# doodle_with_onboard_clock_smd_7805_l293d.net
KiCad netlist of a schematic drawn in EAGLE
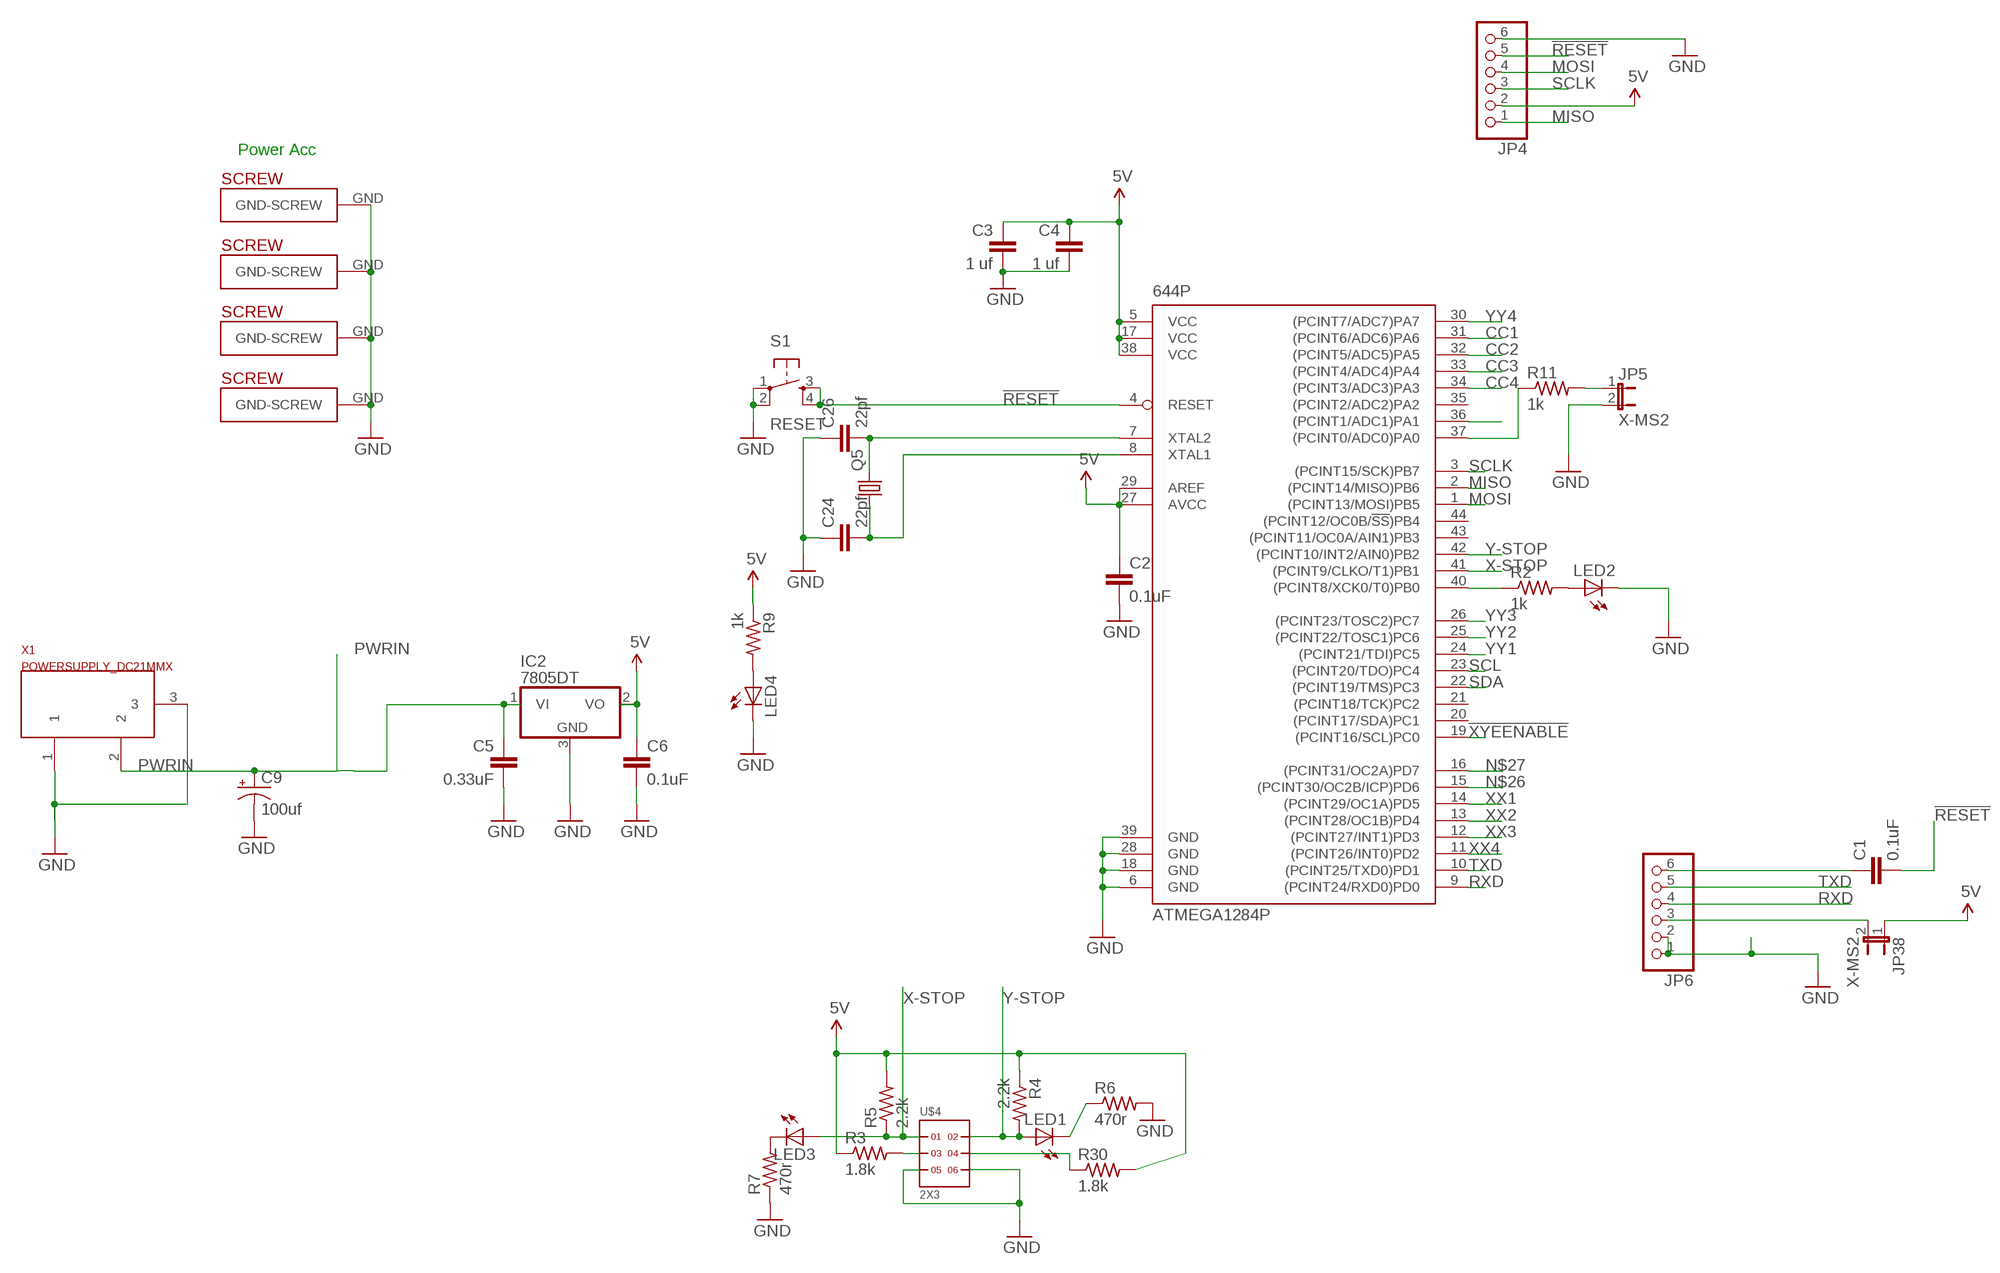
[diagram p0: schematic, sheet 1, part 1 of 2]
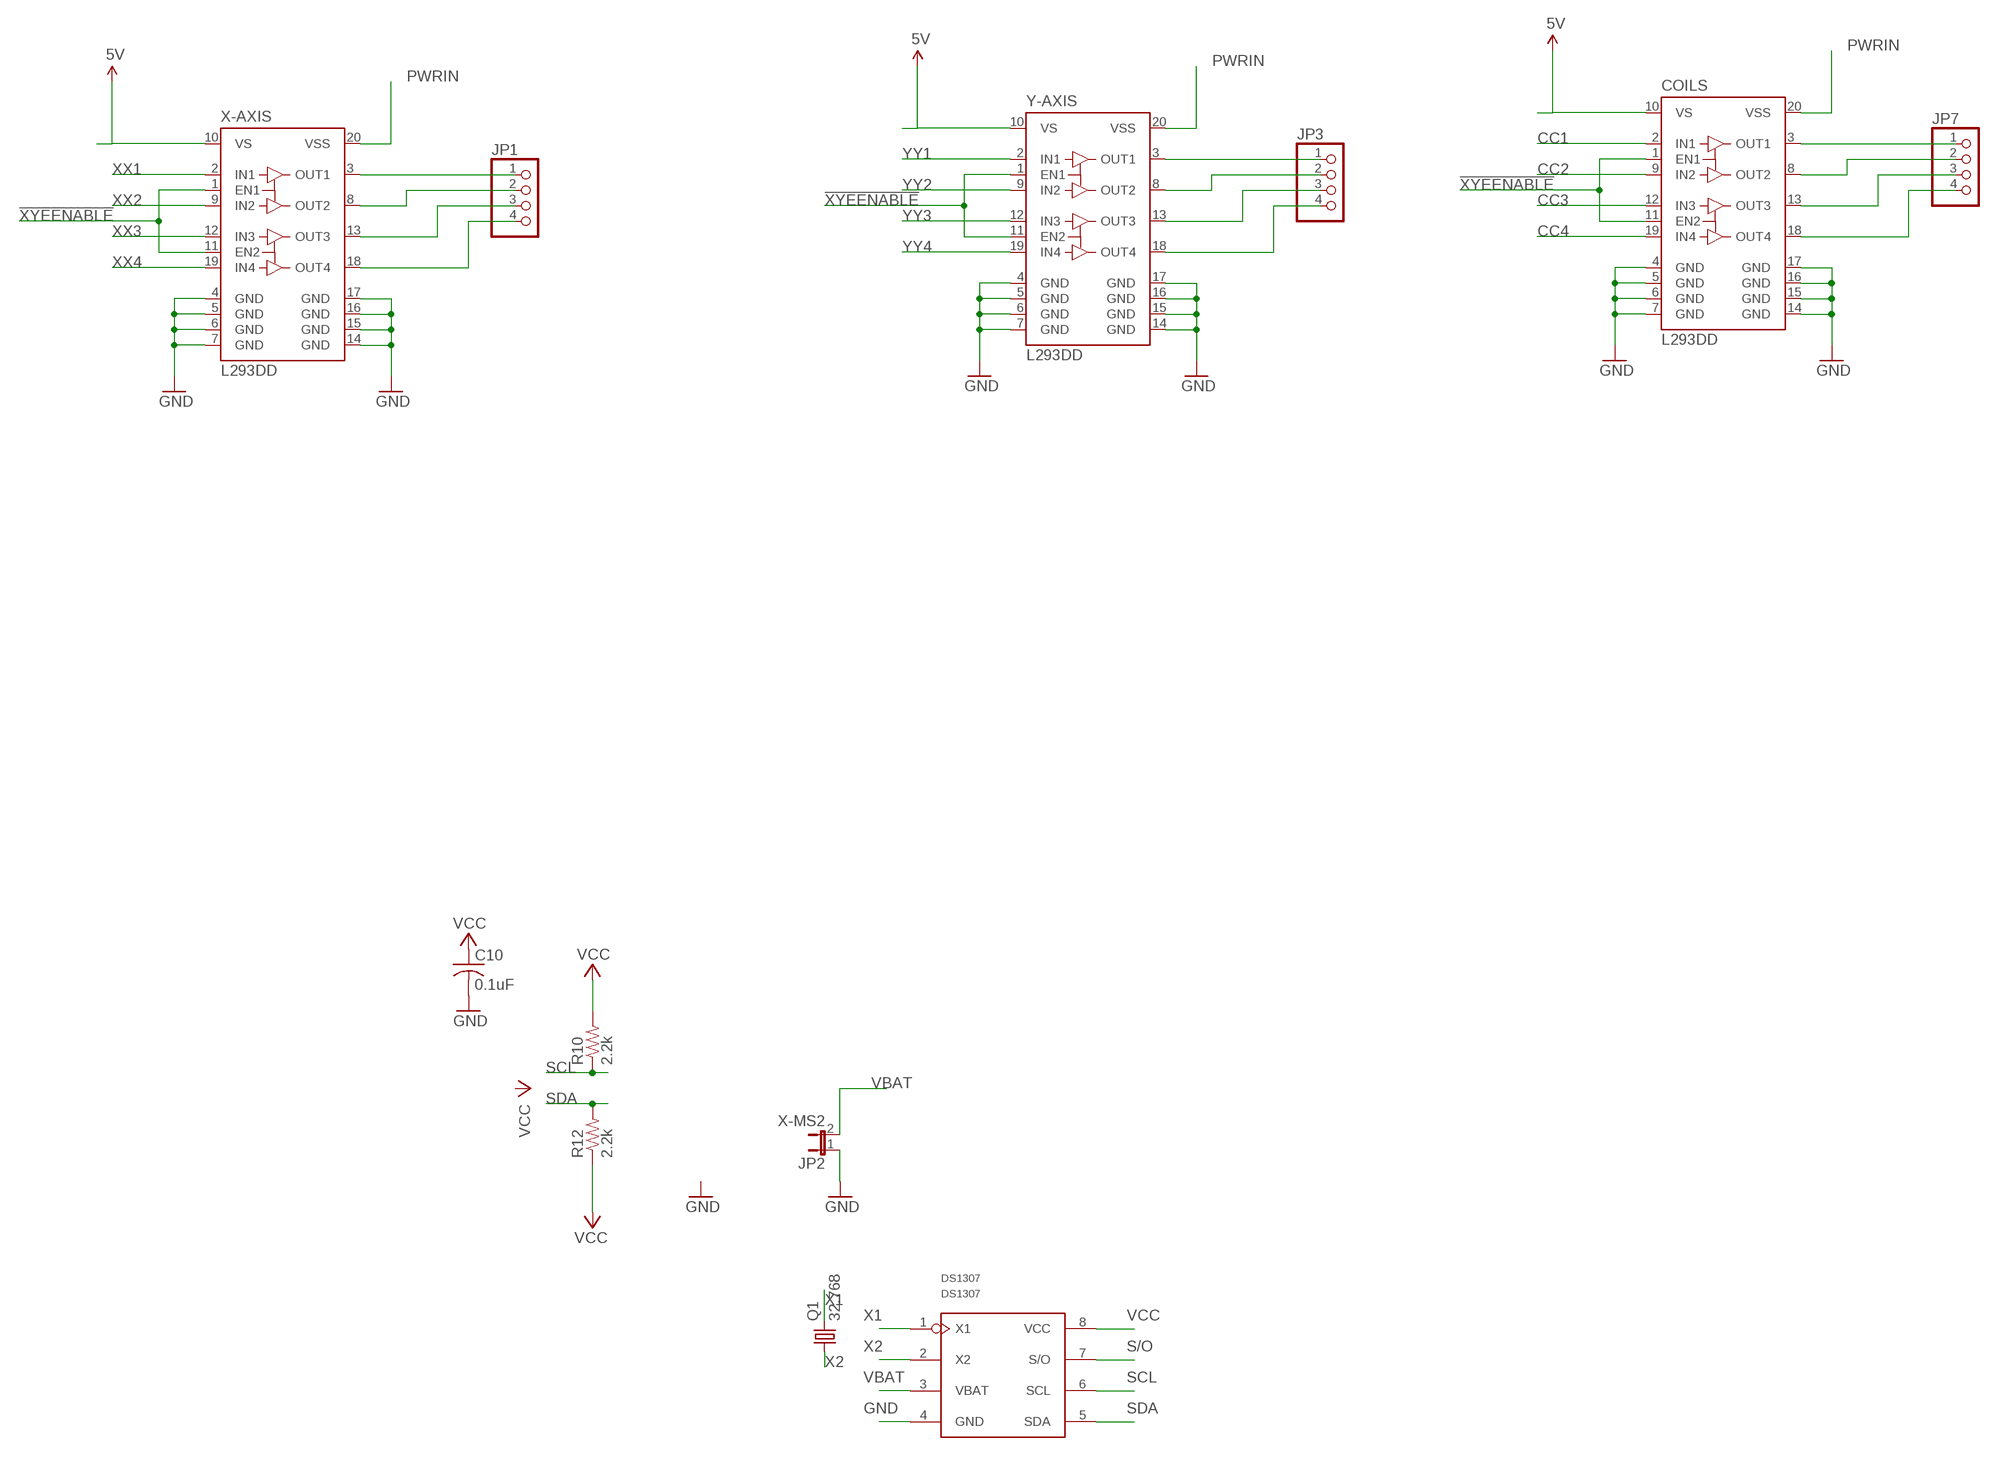
[diagram p1: schematic, sheet 1, part 2 of 2]

(export (version "E")
  (design (tool "Eeschema 10.0.6"))
  (components
    (comp (ref "644P")
      (value "ATMEGA1284P")
      (footprint "eagle-import:TQFP44")
      (fields (field (name "MPN") "ATMEGA644PV-10AU"))
      (libsource (lib "eagle-import") (part "ATMEGA644A"))
    )
    (comp (ref "C1")
      (value "0.1uF")
      (footprint "eagle-import:0805")
      (libsource (lib "eagle-import") (part "CAP0805"))
    )
    (comp (ref "C2")
      (value "0.1uF")
      (footprint "eagle-import:0805")
      (libsource (lib "eagle-import") (part "CAP0805"))
    )
    (comp (ref "C3")
      (value "1 uf")
      (footprint "eagle-import:0805")
      (libsource (lib "eagle-import") (part "CAP0805"))
    )
    (comp (ref "C4")
      (value "1 uf")
      (footprint "eagle-import:0805")
      (libsource (lib "eagle-import") (part "CAP0805"))
    )
    (comp (ref "C5")
      (value "0.33uF")
      (footprint "eagle-import:CAP-PTH-SMALL2")
      (libsource (lib "eagle-import") (part "CAPPTH2"))
    )
    (comp (ref "C6")
      (value "0.1uF")
      (footprint "eagle-import:CAP-PTH-SMALL2")
      (libsource (lib "eagle-import") (part "CAPPTH2"))
    )
    (comp (ref "C9")
      (value "100uf")
      (footprint "eagle-import:CPOL-RADIAL-100UF-25V")
      (libsource (lib "eagle-import") (part "CAP_POLPTH1"))
    )
    (comp (ref "C10")
      (value "0.1uF")
      (footprint "eagle-import:C0805")
      (libsource (lib "eagle-import") (part "C-USC0805"))
    )
    (comp (ref "C24")
      (value "22pf")
      (footprint "eagle-import:0805")
      (libsource (lib "eagle-import") (part "CAP0805"))
    )
    (comp (ref "C26")
      (value "22pf")
      (footprint "eagle-import:0805")
      (libsource (lib "eagle-import") (part "CAP0805"))
    )
    (comp (ref "COILS")
      (value "L293DD")
      (footprint "eagle-import:SO20")
      (libsource (lib "eagle-import") (part "L293DD"))
    )
    (comp (ref "DS1307")
      (value "DS1307")
      (footprint "eagle-import:SO08")
      (libsource (lib "eagle-import") (part "DS1307"))
    )
    (comp (ref "IC2")
      (value "7805DT")
      (footprint "eagle-import:TO252")
      (libsource (lib "eagle-import") (part "78DT05"))
    )
    (comp (ref "JP1")
      (value "PINHD-1X4")
      (footprint "eagle-import:1X04")
      (libsource (lib "eagle-import") (part "PINHD-1X4"))
    )
    (comp (ref "JP2")
      (value "X-MS2")
      (footprint "eagle-import:1X02")
      (libsource (lib "eagle-import") (part "JUMPER-2PTH"))
    )
    (comp (ref "JP3")
      (value "PINHD-1X4")
      (footprint "eagle-import:1X04")
      (libsource (lib "eagle-import") (part "PINHD-1X4"))
    )
    (comp (ref "JP4")
      (value "PINHD-1X6/90")
      (footprint "eagle-import:1X06_90")
      (libsource (lib "eagle-import") (part "PINHD-1X6/90"))
    )
    (comp (ref "JP5")
      (value "X-MS2")
      (footprint "eagle-import:1X02")
      (libsource (lib "eagle-import") (part "JUMPER-2PTH"))
    )
    (comp (ref "JP6")
      (value "PINHD-1X6")
      (footprint "eagle-import:1X06")
      (libsource (lib "eagle-import") (part "PINHD-1X6"))
    )
    (comp (ref "JP7")
      (value "PINHD-1X4")
      (footprint "eagle-import:1X04")
      (libsource (lib "eagle-import") (part "PINHD-1X4"))
    )
    (comp (ref "JP38")
      (value "X-MS2")
      (footprint "eagle-import:1X02")
      (libsource (lib "eagle-import") (part "JUMPER-2PTH"))
    )
    (comp (ref "LED1")
      (value "LEDCHIPLED_0805")
      (footprint "eagle-import:CHIPLED_0805")
      (libsource (lib "eagle-import") (part "LEDCHIPLED_0805"))
    )
    (comp (ref "LED2")
      (value "LEDCHIPLED_0805")
      (footprint "eagle-import:CHIPLED_0805")
      (libsource (lib "eagle-import") (part "LEDCHIPLED_0805"))
    )
    (comp (ref "LED3")
      (value "LEDCHIPLED_0805")
      (footprint "eagle-import:CHIPLED_0805")
      (libsource (lib "eagle-import") (part "LEDCHIPLED_0805"))
    )
    (comp (ref "LED4")
      (value "LEDCHIPLED_0805")
      (footprint "eagle-import:CHIPLED_0805")
      (libsource (lib "eagle-import") (part "LEDCHIPLED_0805"))
    )
    (comp (ref "Q1")
      (value "32.768")
      (footprint "eagle-import:TC38H")
      (libsource (lib "eagle-import") (part "CRYTALTC38H"))
    )
    (comp (ref "Q5")
      (value "CRYSTALHC49S")
      (footprint "eagle-import:HC49_S")
      (libsource (lib "eagle-import") (part "CRYSTALHC49S"))
    )
    (comp (ref "R2")
      (value "1k")
      (footprint "eagle-import:R0805")
      (libsource (lib "eagle-import") (part "R-US_R0805"))
    )
    (comp (ref "R3")
      (value "1.8k")
      (footprint "eagle-import:R0805")
      (libsource (lib "eagle-import") (part "R-US_R0805"))
    )
    (comp (ref "R4")
      (value "2.2k")
      (footprint "eagle-import:R0805")
      (libsource (lib "eagle-import") (part "R-US_R0805"))
    )
    (comp (ref "R5")
      (value "2.2k")
      (footprint "eagle-import:R0805")
      (libsource (lib "eagle-import") (part "R-US_R0805"))
    )
    (comp (ref "R6")
      (value "470r")
      (footprint "eagle-import:R0805")
      (libsource (lib "eagle-import") (part "R-US_R0805"))
    )
    (comp (ref "R7")
      (value "470r")
      (footprint "eagle-import:R0805")
      (libsource (lib "eagle-import") (part "R-US_R0805"))
    )
    (comp (ref "R9")
      (value "1k")
      (footprint "eagle-import:R0805")
      (libsource (lib "eagle-import") (part "R-US_R0805"))
    )
    (comp (ref "R10")
      (value "2.2k")
      (footprint "eagle-import:R0805")
      (libsource (lib "eagle-import") (part "R-US_R0805"))
    )
    (comp (ref "R11")
      (value "1k")
      (footprint "eagle-import:R0805")
      (libsource (lib "eagle-import") (part "R-US_R0805"))
    )
    (comp (ref "R12")
      (value "2.2k")
      (footprint "eagle-import:R0805")
      (libsource (lib "eagle-import") (part "R-US_R0805"))
    )
    (comp (ref "R30")
      (value "1.8k")
      (footprint "eagle-import:R0603")
      (libsource (lib "eagle-import") (part "R-US_R0603"))
    )
    (comp (ref "S1")
      (value "RESET")
      (footprint "eagle-import:TACTILE-PTH")
      (libsource (lib "eagle-import") (part "TAC_SWITCHPTH"))
    )
    (comp (ref "U$4")
      (value "2X3")
      (footprint "eagle-import:2X3")
      (libsource (lib "eagle-import") (part "2X3"))
    )
    (comp (ref "U$14")
      (value "PLATED-SCREW")
      (footprint "eagle-import:PLATEDSCREW")
      (libsource (lib "eagle-import") (part "PLATED-SCREW"))
    )
    (comp (ref "U$17")
      (value "PLATED-SCREW")
      (footprint "eagle-import:PLATEDSCREW")
      (libsource (lib "eagle-import") (part "PLATED-SCREW"))
    )
    (comp (ref "U$18")
      (value "PLATED-SCREW")
      (footprint "eagle-import:PLATEDSCREW")
      (libsource (lib "eagle-import") (part "PLATED-SCREW"))
    )
    (comp (ref "U$38")
      (value "PLATED-SCREW")
      (footprint "eagle-import:PLATEDSCREW")
      (libsource (lib "eagle-import") (part "PLATED-SCREW"))
    )
    (comp (ref "X-AXIS")
      (value "L293DD")
      (footprint "eagle-import:SO20")
      (libsource (lib "eagle-import") (part "L293DD"))
    )
    (comp (ref "X1")
      (value "POWERSUPPLY_DC21MMX")
      (footprint "eagle-import:POWERSUPPLY_DC-21MM")
      (libsource (lib "eagle-import") (part "POWERSUPPLY_DC21MMX"))
    )
    (comp (ref "Y-AXIS")
      (value "L293DD")
      (footprint "eagle-import:SO20")
      (libsource (lib "eagle-import") (part "L293DD"))
    )
  )
  (nets
    (net (code "1") (name "/CC1") (class "Default")
      (node (ref "644P") (pin "31") (pinfunction "(PCINT6/ADC6)PA6_31") (pintype "bidirectional"))
      (node (ref "COILS") (pin "2") (pinfunction "IN1_2") (pintype "input"))
    )
    (net (code "2") (name "/CC2") (class "Default")
      (node (ref "644P") (pin "32") (pinfunction "(PCINT5/ADC5)PA5_32") (pintype "bidirectional"))
      (node (ref "COILS") (pin "9") (pinfunction "IN2_9") (pintype "input"))
    )
    (net (code "3") (name "/CC3") (class "Default")
      (node (ref "644P") (pin "33") (pinfunction "(PCINT4/ADC4)PA4_33") (pintype "bidirectional"))
      (node (ref "COILS") (pin "12") (pinfunction "IN3_12") (pintype "input"))
    )
    (net (code "4") (name "/CC4") (class "Default")
      (node (ref "644P") (pin "34") (pinfunction "(PCINT3/ADC3)PA3_34") (pintype "bidirectional"))
      (node (ref "COILS") (pin "19") (pinfunction "IN4_19") (pintype "input"))
    )
    (net (code "5") (name "/MISO") (class "Default")
      (node (ref "644P") (pin "2") (pinfunction "(PCINT14/MISO)PB6_2") (pintype "bidirectional"))
      (node (ref "JP4") (pin "1") (pinfunction "1_1") (pintype "passive"))
    )
    (net (code "6") (name "/MOSI") (class "Default")
      (node (ref "644P") (pin "1") (pinfunction "(PCINT13/MOSI)PB5_1") (pintype "bidirectional"))
      (node (ref "JP4") (pin "4") (pinfunction "4_4") (pintype "passive"))
    )
    (net (code "7") (name "/N$26") (class "Default")
      (node (ref "644P") (pin "15") (pinfunction "(PCINT30/OC2B/ICP)PD6_15") (pintype "bidirectional"))
    )
    (net (code "8") (name "/N$27") (class "Default")
      (node (ref "644P") (pin "16") (pinfunction "(PCINT31/OC2A)PD7_16") (pintype "bidirectional"))
    )
    (net (code "9") (name "/PWRIN") (class "Default")
      (node (ref "C5") (pin "1") (pinfunction "1_1") (pintype "passive"))
      (node (ref "C9") (pin "1") (pinfunction "+_1") (pintype "passive"))
      (node (ref "COILS") (pin "20") (pinfunction "VSS_20") (pintype "power_in"))
      (node (ref "IC2") (pin "1") (pinfunction "VI_1") (pintype "input"))
      (node (ref "X-AXIS") (pin "20") (pinfunction "VSS_20") (pintype "power_in"))
      (node (ref "X1") (pin "2") (pinfunction "2_2") (pintype "power_in"))
      (node (ref "Y-AXIS") (pin "20") (pinfunction "VSS_20") (pintype "power_in"))
    )
    (net (code "10") (name "/RXD") (class "Default")
      (node (ref "644P") (pin "9") (pinfunction "(PCINT24/RXD0)PD0_9") (pintype "bidirectional"))
      (node (ref "JP6") (pin "4") (pinfunction "4_4") (pintype "passive"))
    )
    (net (code "11") (name "/SCL") (class "Default")
      (node (ref "644P") (pin "23") (pinfunction "(PCINT20/TDO)PC4_23") (pintype "output"))
      (node (ref "DS1307") (pin "6") (pinfunction "SCL_6") (pintype "bidirectional"))
      (node (ref "R10") (pin "1") (pinfunction "1_1") (pintype "passive"))
    )
    (net (code "12") (name "/SCLK") (class "Default")
      (node (ref "644P") (pin "3") (pinfunction "(PCINT15/SCK)PB7_3") (pintype "bidirectional"))
      (node (ref "JP4") (pin "3") (pinfunction "3_3") (pintype "passive"))
    )
    (net (code "13") (name "/SDA") (class "Default")
      (node (ref "644P") (pin "22") (pinfunction "(PCINT19/TMS)PC3_22") (pintype "output"))
      (node (ref "DS1307") (pin "5") (pinfunction "SDA_5") (pintype "bidirectional"))
      (node (ref "R12") (pin "2") (pinfunction "2_2") (pintype "passive"))
    )
    (net (code "14") (name "/S{slash}O") (class "Default")
      (node (ref "DS1307") (pin "7") (pinfunction "S/O_7") (pintype "bidirectional"))
    )
    (net (code "15") (name "/TXD") (class "Default")
      (node (ref "644P") (pin "10") (pinfunction "(PCINT25/TXD0)PD1_10") (pintype "bidirectional"))
      (node (ref "JP6") (pin "5") (pinfunction "5_5") (pintype "passive"))
    )
    (net (code "16") (name "/VBAT") (class "Default")
      (node (ref "DS1307") (pin "3") (pinfunction "VBAT_3") (pintype "bidirectional"))
      (node (ref "JP2") (pin "2") (pinfunction "2_2") (pintype "passive"))
    )
    (net (code "17") (name "/X-STOP") (class "Default")
      (node (ref "644P") (pin "41") (pinfunction "(PCINT9/CLKO/T1)PB1_41") (pintype "bidirectional"))
      (node (ref "LED3") (pin "A") (pinfunction "A_A") (pintype "passive"))
      (node (ref "R5") (pin "1") (pinfunction "1_1") (pintype "passive"))
      (node (ref "U$4") (pin "1") (pinfunction "1_1") (pintype "bidirectional"))
    )
    (net (code "18") (name "/X1") (class "Default")
      (node (ref "DS1307") (pin "1") (pinfunction "X1_1") (pintype "bidirectional"))
      (node (ref "Q1") (pin "2") (pinfunction "2_2") (pintype "passive"))
    )
    (net (code "19") (name "/X2") (class "Default")
      (node (ref "DS1307") (pin "2") (pinfunction "X2_2") (pintype "bidirectional"))
      (node (ref "Q1") (pin "1") (pinfunction "1_1") (pintype "passive"))
    )
    (net (code "20") (name "/XX1") (class "Default")
      (node (ref "644P") (pin "14") (pinfunction "(PCINT29/OC1A)PD5_14") (pintype "bidirectional"))
      (node (ref "X-AXIS") (pin "2") (pinfunction "IN1_2") (pintype "input"))
    )
    (net (code "21") (name "/XX2") (class "Default")
      (node (ref "644P") (pin "13") (pinfunction "(PCINT28/OC1B)PD4_13") (pintype "bidirectional"))
      (node (ref "X-AXIS") (pin "9") (pinfunction "IN2_9") (pintype "input"))
    )
    (net (code "22") (name "/XX3") (class "Default")
      (node (ref "644P") (pin "12") (pinfunction "(PCINT27/INT1)PD3_12") (pintype "bidirectional"))
      (node (ref "X-AXIS") (pin "12") (pinfunction "IN3_12") (pintype "input"))
    )
    (net (code "23") (name "/XX4") (class "Default")
      (node (ref "644P") (pin "11") (pinfunction "(PCINT26/INT0)PD2_11") (pintype "bidirectional"))
      (node (ref "X-AXIS") (pin "19") (pinfunction "IN4_19") (pintype "input"))
    )
    (net (code "24") (name "/Y-STOP") (class "Default")
      (node (ref "644P") (pin "42") (pinfunction "(PCINT10/INT2/AIN0)PB2_42") (pintype "bidirectional"))
      (node (ref "LED1") (pin "A") (pinfunction "A_A") (pintype "passive"))
      (node (ref "R4") (pin "2") (pinfunction "2_2") (pintype "passive"))
      (node (ref "U$4") (pin "2") (pinfunction "2_2") (pintype "bidirectional"))
    )
    (net (code "25") (name "/YY1") (class "Default")
      (node (ref "644P") (pin "24") (pinfunction "(PCINT21/TDI)PC5_24") (pintype "output"))
      (node (ref "Y-AXIS") (pin "2") (pinfunction "IN1_2") (pintype "input"))
    )
    (net (code "26") (name "/YY2") (class "Default")
      (node (ref "644P") (pin "25") (pinfunction "(PCINT22/TOSC1)PC6_25") (pintype "output"))
      (node (ref "Y-AXIS") (pin "9") (pinfunction "IN2_9") (pintype "input"))
    )
    (net (code "27") (name "/YY3") (class "Default")
      (node (ref "644P") (pin "26") (pinfunction "(PCINT23/TOSC2)PC7_26") (pintype "output"))
      (node (ref "Y-AXIS") (pin "12") (pinfunction "IN3_12") (pintype "input"))
    )
    (net (code "28") (name "/YY4") (class "Default")
      (node (ref "644P") (pin "30") (pinfunction "(PCINT7/ADC7)PA7_30") (pintype "bidirectional"))
      (node (ref "Y-AXIS") (pin "19") (pinfunction "IN4_19") (pintype "input"))
    )
    (net (code "29") (name "/~{RESET}") (class "Default")
      (node (ref "644P") (pin "4") (pinfunction "RESET_4") (pintype "input"))
      (node (ref "C1") (pin "2") (pinfunction "2_2") (pintype "passive"))
      (node (ref "JP4") (pin "5") (pinfunction "5_5") (pintype "passive"))
      (node (ref "S1") (pin "3") (pinfunction "3_3") (pintype "passive"))
      (node (ref "S1") (pin "4") (pinfunction "4_4") (pintype "passive"))
    )
    (net (code "30") (name "/~{XYEENABLE}") (class "Default")
      (node (ref "644P") (pin "19") (pinfunction "(PCINT16/SCL)PC0_19") (pintype "output"))
      (node (ref "COILS") (pin "1") (pinfunction "EN1_1") (pintype "input"))
      (node (ref "COILS") (pin "11") (pinfunction "EN2_11") (pintype "input"))
      (node (ref "X-AXIS") (pin "1") (pinfunction "EN1_1") (pintype "input"))
      (node (ref "X-AXIS") (pin "11") (pinfunction "EN2_11") (pintype "input"))
      (node (ref "Y-AXIS") (pin "1") (pinfunction "EN1_1") (pintype "input"))
      (node (ref "Y-AXIS") (pin "11") (pinfunction "EN2_11") (pintype "input"))
    )
    (net (code "31") (name "5V") (class "Default")
      (node (ref "644P") (pin "17") (pinfunction "VCC_17") (pintype "power_in"))
      (node (ref "644P") (pin "27") (pinfunction "AVCC_27") (pintype "power_in"))
      (node (ref "644P") (pin "29") (pinfunction "AREF_29") (pintype "passive"))
      (node (ref "644P") (pin "38") (pinfunction "VCC_38") (pintype "power_in"))
      (node (ref "644P") (pin "5") (pinfunction "VCC_5") (pintype "power_in"))
      (node (ref "C2") (pin "1") (pinfunction "1_1") (pintype "passive"))
      (node (ref "C3") (pin "1") (pinfunction "1_1") (pintype "passive"))
      (node (ref "C4") (pin "1") (pinfunction "1_1") (pintype "passive"))
      (node (ref "C6") (pin "1") (pinfunction "1_1") (pintype "passive"))
      (node (ref "COILS") (pin "10") (pinfunction "VS_10") (pintype "power_in"))
      (node (ref "IC2") (pin "2") (pinfunction "VO_2") (pintype "passive"))
      (node (ref "JP38") (pin "1") (pinfunction "1_1") (pintype "passive"))
      (node (ref "JP4") (pin "2") (pinfunction "2_2") (pintype "passive"))
      (node (ref "R3") (pin "1") (pinfunction "1_1") (pintype "passive"))
      (node (ref "R30") (pin "2") (pinfunction "2_2") (pintype "passive"))
      (node (ref "R4") (pin "1") (pinfunction "1_1") (pintype "passive"))
      (node (ref "R5") (pin "2") (pinfunction "2_2") (pintype "passive"))
      (node (ref "R9") (pin "1") (pinfunction "1_1") (pintype "passive"))
      (node (ref "X-AXIS") (pin "10") (pinfunction "VS_10") (pintype "power_in"))
      (node (ref "Y-AXIS") (pin "10") (pinfunction "VS_10") (pintype "power_in"))
    )
    (net (code "32") (name "GND") (class "Default")
      (node (ref "644P") (pin "18") (pinfunction "GND_18") (pintype "power_in"))
      (node (ref "644P") (pin "28") (pinfunction "GND_28") (pintype "power_in"))
      (node (ref "644P") (pin "39") (pinfunction "GND_39") (pintype "power_in"))
      (node (ref "644P") (pin "6") (pinfunction "GND_6") (pintype "power_in"))
      (node (ref "C10") (pin "2") (pinfunction "2_2") (pintype "passive"))
      (node (ref "C2") (pin "2") (pinfunction "2_2") (pintype "passive"))
      (node (ref "C24") (pin "1") (pinfunction "1_1") (pintype "passive"))
      (node (ref "C26") (pin "1") (pinfunction "1_1") (pintype "passive"))
      (node (ref "C3") (pin "2") (pinfunction "2_2") (pintype "passive"))
      (node (ref "C4") (pin "2") (pinfunction "2_2") (pintype "passive"))
      (node (ref "C5") (pin "2") (pinfunction "2_2") (pintype "passive"))
      (node (ref "C6") (pin "2") (pinfunction "2_2") (pintype "passive"))
      (node (ref "C9") (pin "2") (pinfunction "-_2") (pintype "passive"))
      (node (ref "COILS") (pin "14") (pinfunction "GND_14") (pintype "power_in"))
      (node (ref "COILS") (pin "15") (pinfunction "GND_15") (pintype "power_in"))
      (node (ref "COILS") (pin "16") (pinfunction "GND_16") (pintype "power_in"))
      (node (ref "COILS") (pin "17") (pinfunction "GND_17") (pintype "power_in"))
      (node (ref "COILS") (pin "4") (pinfunction "GND_4") (pintype "power_in"))
      (node (ref "COILS") (pin "5") (pinfunction "GND_5") (pintype "power_in"))
      (node (ref "COILS") (pin "6") (pinfunction "GND_6") (pintype "power_in"))
      (node (ref "COILS") (pin "7") (pinfunction "GND_7") (pintype "power_in"))
      (node (ref "DS1307") (pin "4") (pinfunction "GND_4") (pintype "bidirectional"))
      (node (ref "IC2") (pin "3") (pinfunction "GND_3") (pintype "passive"))
      (node (ref "JP2") (pin "1") (pinfunction "1_1") (pintype "passive"))
      (node (ref "JP4") (pin "6") (pinfunction "6_6") (pintype "passive"))
      (node (ref "JP5") (pin "2") (pinfunction "2_2") (pintype "passive"))
      (node (ref "JP6") (pin "1") (pinfunction "1_1") (pintype "passive"))
      (node (ref "JP6") (pin "2") (pinfunction "2_2") (pintype "passive"))
      (node (ref "LED2") (pin "C") (pinfunction "C_C") (pintype "passive"))
      (node (ref "LED4") (pin "C") (pinfunction "C_C") (pintype "passive"))
      (node (ref "R6") (pin "2") (pinfunction "2_2") (pintype "passive"))
      (node (ref "R7") (pin "1") (pinfunction "1_1") (pintype "passive"))
      (node (ref "S1") (pin "1") (pinfunction "1_1") (pintype "passive"))
      (node (ref "S1") (pin "2") (pinfunction "2_2") (pintype "passive"))
      (node (ref "U$14") (pin "GND") (pinfunction "GND-SCREW_GND") (pintype "bidirectional"))
      (node (ref "U$17") (pin "GND") (pinfunction "GND-SCREW_GND") (pintype "bidirectional"))
      (node (ref "U$18") (pin "GND") (pinfunction "GND-SCREW_GND") (pintype "bidirectional"))
      (node (ref "U$38") (pin "GND") (pinfunction "GND-SCREW_GND") (pintype "bidirectional"))
      (node (ref "U$4") (pin "5") (pinfunction "5_5") (pintype "bidirectional"))
      (node (ref "U$4") (pin "6") (pinfunction "6_6") (pintype "bidirectional"))
      (node (ref "X-AXIS") (pin "14") (pinfunction "GND_14") (pintype "power_in"))
      (node (ref "X-AXIS") (pin "15") (pinfunction "GND_15") (pintype "power_in"))
      (node (ref "X-AXIS") (pin "16") (pinfunction "GND_16") (pintype "power_in"))
      (node (ref "X-AXIS") (pin "17") (pinfunction "GND_17") (pintype "power_in"))
      (node (ref "X-AXIS") (pin "4") (pinfunction "GND_4") (pintype "power_in"))
      (node (ref "X-AXIS") (pin "5") (pinfunction "GND_5") (pintype "power_in"))
      (node (ref "X-AXIS") (pin "6") (pinfunction "GND_6") (pintype "power_in"))
      (node (ref "X-AXIS") (pin "7") (pinfunction "GND_7") (pintype "power_in"))
      (node (ref "X1") (pin "1") (pinfunction "1_1") (pintype "power_in"))
      (node (ref "X1") (pin "3") (pinfunction "3_3") (pintype "power_in"))
      (node (ref "Y-AXIS") (pin "14") (pinfunction "GND_14") (pintype "power_in"))
      (node (ref "Y-AXIS") (pin "15") (pinfunction "GND_15") (pintype "power_in"))
      (node (ref "Y-AXIS") (pin "16") (pinfunction "GND_16") (pintype "power_in"))
      (node (ref "Y-AXIS") (pin "17") (pinfunction "GND_17") (pintype "power_in"))
      (node (ref "Y-AXIS") (pin "4") (pinfunction "GND_4") (pintype "power_in"))
      (node (ref "Y-AXIS") (pin "5") (pinfunction "GND_5") (pintype "power_in"))
      (node (ref "Y-AXIS") (pin "6") (pinfunction "GND_6") (pintype "power_in"))
      (node (ref "Y-AXIS") (pin "7") (pinfunction "GND_7") (pintype "power_in"))
    )
    (net (code "33") (name "Net-(644P-(PCINT0{slash}ADC0)PA0)") (class "Default")
      (node (ref "644P") (pin "37") (pinfunction "(PCINT0/ADC0)PA0_37") (pintype "bidirectional"))
      (node (ref "R11") (pin "1") (pinfunction "1_1") (pintype "passive"))
    )
    (net (code "34") (name "Net-(644P-(PCINT8{slash}XCK0{slash}T0)PB0)") (class "Default")
      (node (ref "644P") (pin "40") (pinfunction "(PCINT8/XCK0/T0)PB0_40") (pintype "bidirectional"))
      (node (ref "R2") (pin "1") (pinfunction "1_1") (pintype "passive"))
    )
    (net (code "35") (name "Net-(644P-XTAL1)") (class "Default")
      (node (ref "644P") (pin "8") (pinfunction "XTAL1_8") (pintype "bidirectional"))
      (node (ref "C24") (pin "2") (pinfunction "2_2") (pintype "passive"))
      (node (ref "Q5") (pin "1") (pinfunction "1_1") (pintype "passive"))
    )
    (net (code "36") (name "Net-(644P-XTAL2)") (class "Default")
      (node (ref "644P") (pin "7") (pinfunction "XTAL2_7") (pintype "bidirectional"))
      (node (ref "C26") (pin "2") (pinfunction "2_2") (pintype "passive"))
      (node (ref "Q5") (pin "2") (pinfunction "2_2") (pintype "passive"))
    )
    (net (code "37") (name "Net-(C1-Pad1)") (class "Default")
      (node (ref "C1") (pin "1") (pinfunction "1_1") (pintype "passive"))
      (node (ref "JP6") (pin "6") (pinfunction "6_6") (pintype "passive"))
    )
    (net (code "38") (name "Net-(COILS-OUT1)") (class "Default")
      (node (ref "COILS") (pin "3") (pinfunction "OUT1_3") (pintype "output"))
      (node (ref "JP7") (pin "1") (pinfunction "1_1") (pintype "passive"))
    )
    (net (code "39") (name "Net-(COILS-OUT2)") (class "Default")
      (node (ref "COILS") (pin "8") (pinfunction "OUT2_8") (pintype "output"))
      (node (ref "JP7") (pin "2") (pinfunction "2_2") (pintype "passive"))
    )
    (net (code "40") (name "Net-(COILS-OUT3)") (class "Default")
      (node (ref "COILS") (pin "13") (pinfunction "OUT3_13") (pintype "output"))
      (node (ref "JP7") (pin "3") (pinfunction "3_3") (pintype "passive"))
    )
    (net (code "41") (name "Net-(COILS-OUT4)") (class "Default")
      (node (ref "COILS") (pin "18") (pinfunction "OUT4_18") (pintype "output"))
      (node (ref "JP7") (pin "4") (pinfunction "4_4") (pintype "passive"))
    )
    (net (code "42") (name "Net-(JP5-Pad1)") (class "Default")
      (node (ref "JP5") (pin "1") (pinfunction "1_1") (pintype "passive"))
      (node (ref "R11") (pin "2") (pinfunction "2_2") (pintype "passive"))
    )
    (net (code "43") (name "Net-(JP38-Pad2)") (class "Default")
      (node (ref "JP38") (pin "2") (pinfunction "2_2") (pintype "passive"))
      (node (ref "JP6") (pin "3") (pinfunction "3_3") (pintype "passive"))
    )
    (net (code "44") (name "Net-(LED1-PadC)") (class "Default")
      (node (ref "LED1") (pin "C") (pinfunction "C_C") (pintype "passive"))
      (node (ref "R6") (pin "1") (pinfunction "1_1") (pintype "passive"))
    )
    (net (code "45") (name "Net-(LED2-PadA)") (class "Default")
      (node (ref "LED2") (pin "A") (pinfunction "A_A") (pintype "passive"))
      (node (ref "R2") (pin "2") (pinfunction "2_2") (pintype "passive"))
    )
    (net (code "46") (name "Net-(LED3-PadC)") (class "Default")
      (node (ref "LED3") (pin "C") (pinfunction "C_C") (pintype "passive"))
      (node (ref "R7") (pin "2") (pinfunction "2_2") (pintype "passive"))
    )
    (net (code "47") (name "Net-(LED4-PadA)") (class "Default")
      (node (ref "LED4") (pin "A") (pinfunction "A_A") (pintype "passive"))
      (node (ref "R9") (pin "2") (pinfunction "2_2") (pintype "passive"))
    )
    (net (code "48") (name "Net-(R3-Pad2)") (class "Default")
      (node (ref "R3") (pin "2") (pinfunction "2_2") (pintype "passive"))
      (node (ref "U$4") (pin "3") (pinfunction "3_3") (pintype "bidirectional"))
    )
    (net (code "49") (name "Net-(R30-Pad1)") (class "Default")
      (node (ref "R30") (pin "1") (pinfunction "1_1") (pintype "passive"))
      (node (ref "U$4") (pin "4") (pinfunction "4_4") (pintype "bidirectional"))
    )
    (net (code "50") (name "Net-(X-AXIS-OUT1)") (class "Default")
      (node (ref "JP1") (pin "1") (pinfunction "1_1") (pintype "passive"))
      (node (ref "X-AXIS") (pin "3") (pinfunction "OUT1_3") (pintype "output"))
    )
    (net (code "51") (name "Net-(X-AXIS-OUT2)") (class "Default")
      (node (ref "JP1") (pin "2") (pinfunction "2_2") (pintype "passive"))
      (node (ref "X-AXIS") (pin "8") (pinfunction "OUT2_8") (pintype "output"))
    )
    (net (code "52") (name "Net-(X-AXIS-OUT3)") (class "Default")
      (node (ref "JP1") (pin "3") (pinfunction "3_3") (pintype "passive"))
      (node (ref "X-AXIS") (pin "13") (pinfunction "OUT3_13") (pintype "output"))
    )
    (net (code "53") (name "Net-(X-AXIS-OUT4)") (class "Default")
      (node (ref "JP1") (pin "4") (pinfunction "4_4") (pintype "passive"))
      (node (ref "X-AXIS") (pin "18") (pinfunction "OUT4_18") (pintype "output"))
    )
    (net (code "54") (name "Net-(Y-AXIS-OUT1)") (class "Default")
      (node (ref "JP3") (pin "1") (pinfunction "1_1") (pintype "passive"))
      (node (ref "Y-AXIS") (pin "3") (pinfunction "OUT1_3") (pintype "output"))
    )
    (net (code "55") (name "Net-(Y-AXIS-OUT2)") (class "Default")
      (node (ref "JP3") (pin "2") (pinfunction "2_2") (pintype "passive"))
      (node (ref "Y-AXIS") (pin "8") (pinfunction "OUT2_8") (pintype "output"))
    )
    (net (code "56") (name "Net-(Y-AXIS-OUT3)") (class "Default")
      (node (ref "JP3") (pin "3") (pinfunction "3_3") (pintype "passive"))
      (node (ref "Y-AXIS") (pin "13") (pinfunction "OUT3_13") (pintype "output"))
    )
    (net (code "57") (name "Net-(Y-AXIS-OUT4)") (class "Default")
      (node (ref "JP3") (pin "4") (pinfunction "4_4") (pintype "passive"))
      (node (ref "Y-AXIS") (pin "18") (pinfunction "OUT4_18") (pintype "output"))
    )
    (net (code "58") (name "VCC") (class "Default")
      (node (ref "C10") (pin "1") (pinfunction "1_1") (pintype "passive"))
      (node (ref "DS1307") (pin "8") (pinfunction "VCC_8") (pintype "bidirectional"))
      (node (ref "R10") (pin "2") (pinfunction "2_2") (pintype "passive"))
      (node (ref "R12") (pin "1") (pinfunction "1_1") (pintype "passive"))
    )
    (net (code "59") (name "unconnected-(644P-(PCINT1{slash}ADC1)PA1-Pad36)") (class "Default")
      (node (ref "644P") (pin "36") (pinfunction "(PCINT1/ADC1)PA1_36") (pintype "bidirectional"))
    )
    (net (code "60") (name "unconnected-(644P-(PCINT2{slash}ADC2)PA2-Pad35)") (class "Default")
      (node (ref "644P") (pin "35") (pinfunction "(PCINT2/ADC2)PA2_35") (pintype "bidirectional"))
    )
    (net (code "61") (name "unconnected-(644P-(PCINT11{slash}OC0A{slash}AIN1)PB3-Pad43)") (class "Default")
      (node (ref "644P") (pin "43") (pinfunction "(PCINT11/OC0A/AIN1)PB3_43") (pintype "bidirectional"))
    )
    (net (code "62") (name "unconnected-(644P-(PCINT12{slash}OC0B{slash}~{SS})PB4-Pad44)") (class "Default")
      (node (ref "644P") (pin "44") (pinfunction "(PCINT12/OC0B/~{SS})PB4_44") (pintype "bidirectional"))
    )
    (net (code "63") (name "unconnected-(644P-(PCINT17{slash}SDA)PC1-Pad20)") (class "Default")
      (node (ref "644P") (pin "20") (pinfunction "(PCINT17/SDA)PC1_20") (pintype "output"))
    )
    (net (code "64") (name "unconnected-(644P-(PCINT18{slash}TCK)PC2-Pad21)") (class "Default")
      (node (ref "644P") (pin "21") (pinfunction "(PCINT18/TCK)PC2_21") (pintype "output"))
    )
  )
)
